# ControllerV1_0_2.net
KiCad netlist of a schematic drawn in Altium Designer
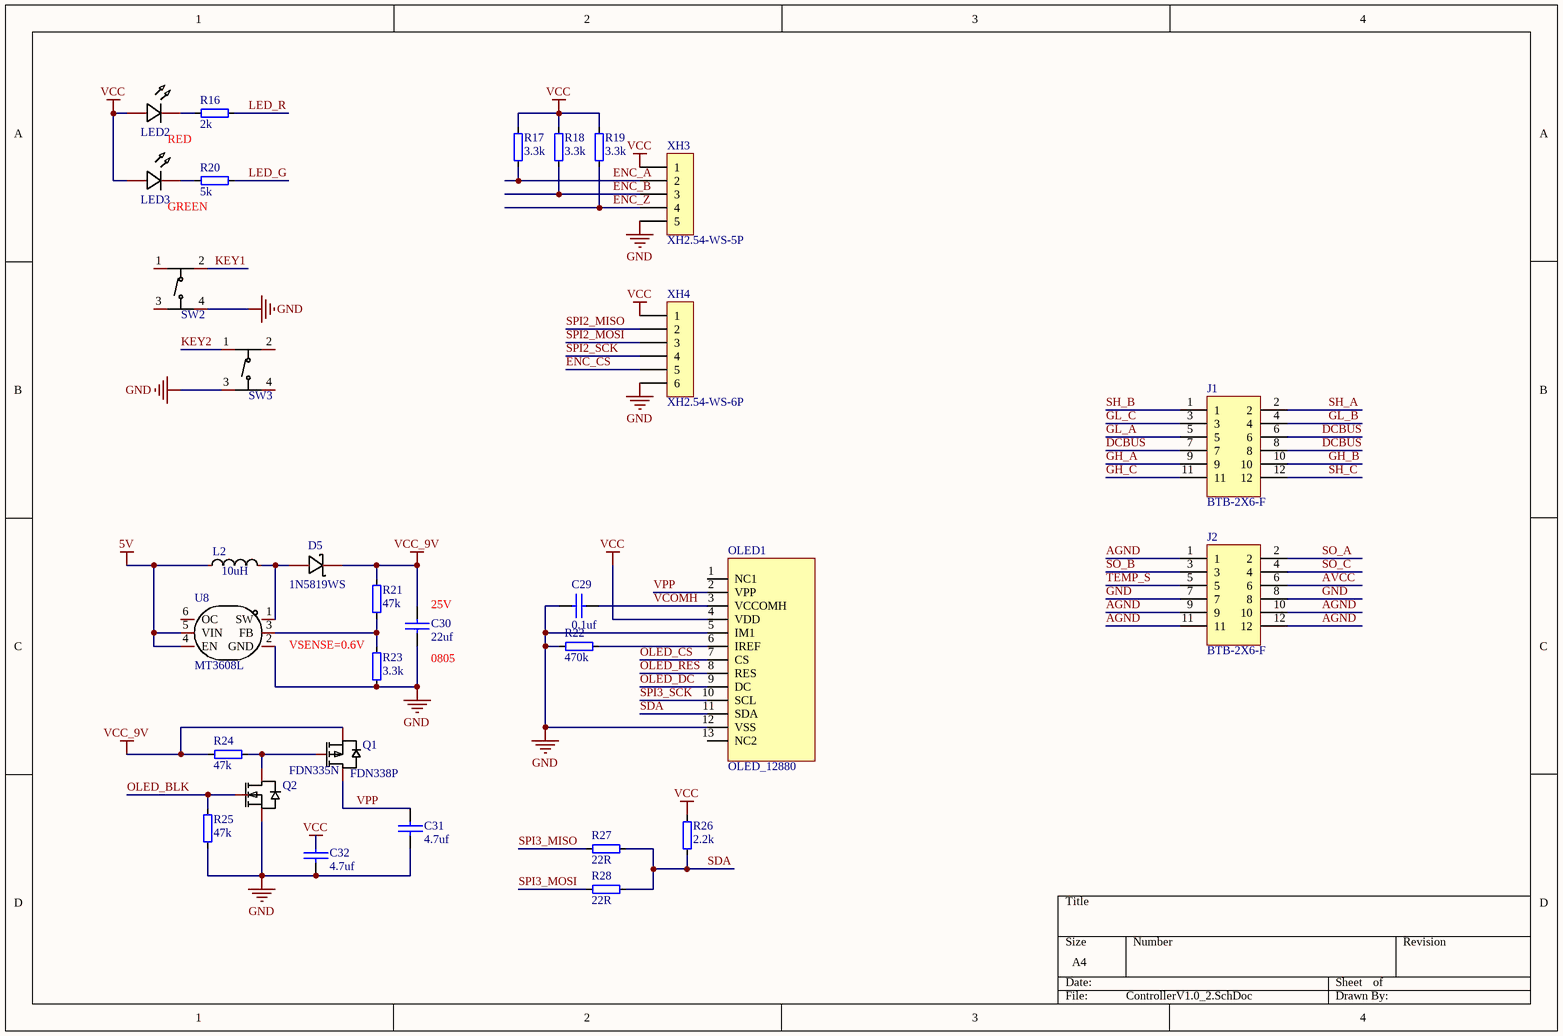
[diagram p0: ControllerV1.0_2.SchDoc]

(export (version "E")
  (design (tool "Eeschema 10.0.6"))
  (components
    (comp (ref "C29")
      (value "0.1uf")
      (footprint "0603C")
      (description "贴片电容")
      (libsource (lib "Controller") (part "CAP"))
    )
    (comp (ref "C30")
      (value "22uf")
      (footprint "0805C")
      (description "贴片电容")
      (libsource (lib "Controller") (part "CAP"))
    )
    (comp (ref "C31")
      (value "4.7uf")
      (footprint "0603C")
      (description "贴片电容")
      (libsource (lib "Controller") (part "CAP"))
    )
    (comp (ref "C32")
      (value "4.7uf")
      (footprint "0603C")
      (description "贴片电容")
      (libsource (lib "Controller") (part "CAP"))
    )
    (comp (ref "D5")
      (value "1N5819WS")
      (footprint "SOD-323")
      (description "肖特基二极管")
      (fields (field (name "MANUFACTURER") "Hottech(合科泰)"))
      (libsource (lib "Controller") (part "1N5819WS"))
    )
    (comp (ref "J1")
      (value "BTB-2X6-F")
      (footprint "BTB-F-0.8mm-2x6P")
      (description "0.8间距2x6P母座")
      (libsource (lib "Controller") (part "BTB-2X6-F"))
    )
    (comp (ref "J2")
      (value "BTB-2X6-F")
      (footprint "BTB-F-0.8mm-2x6P")
      (description "0.8间距2x6P母座")
      (libsource (lib "Controller") (part "BTB-2X6-F"))
    )
    (comp (ref "L2")
      (value "10uH")
      (footprint "IND-SMD_L3.0-W3.0_SWPA3010S")
      (description "电感值:10uH;精度:±20%;额定电流:920mA;")
      (fields (field (name "MANUFACTURER") "SXN(顺翔诺)") (field (name "MANUFACTURER PART") "SMDRI74-220M"))
      (libsource (lib "Controller") (part "SWPA3015S100MT"))
    )
    (comp (ref "LED2")
      (value "LED_0603-B")
      (footprint "LED_0603")
      (libsource (lib "Controller") (part "LED"))
    )
    (comp (ref "LED3")
      (value "LED_0603-B")
      (footprint "LED_0603")
      (libsource (lib "Controller") (part "LED"))
    )
    (comp (ref "OLED1")
      (value "OLED_12880")
      (footprint "OLED_12880")
      (description "OLED_128*80")
      (libsource (lib "Controller") (part "OLED_12880"))
    )
    (comp (ref "Q1")
      (value "FDN338P")
      (footprint "SOT-23-3")
      (description "P沟道 耐压:20V 电流:2A")
      (fields (field (name "MANUFACTURER") "TECH PUBLIC(台舟)"))
      (libsource (lib "Controller") (part "FDN338P"))
    )
    (comp (ref "Q2")
      (value "FDN335N")
      (footprint "SOT-23-3")
      (description "N沟道 耐压:20V 电流:1.7A")
      (fields (field (name "MANUFACTURER") "TECH PUBLIC(台舟)"))
      (libsource (lib "Controller") (part "FDN335N"))
    )
    (comp (ref "R16")
      (value "2k")
      (footprint "0603R")
      (description "贴片电阻")
      (libsource (lib "Controller") (part "RES"))
    )
    (comp (ref "R17")
      (value "3.3k")
      (footprint "0603R")
      (description "贴片电阻")
      (libsource (lib "Controller") (part "RES"))
    )
    (comp (ref "R18")
      (value "3.3k")
      (footprint "0603R")
      (description "贴片电阻")
      (libsource (lib "Controller") (part "RES"))
    )
    (comp (ref "R19")
      (value "3.3k")
      (footprint "0603R")
      (description "贴片电阻")
      (libsource (lib "Controller") (part "RES"))
    )
    (comp (ref "R20")
      (value "5k")
      (footprint "0603R")
      (description "贴片电阻")
      (libsource (lib "Controller") (part "RES"))
    )
    (comp (ref "R21")
      (value "47k")
      (footprint "0603R")
      (description "贴片电阻")
      (libsource (lib "Controller") (part "RES"))
    )
    (comp (ref "R22")
      (value "470k")
      (footprint "0603R")
      (description "贴片电阻")
      (libsource (lib "Controller") (part "RES"))
    )
    (comp (ref "R23")
      (value "3.3k")
      (footprint "0603R")
      (description "贴片电阻")
      (libsource (lib "Controller") (part "RES"))
    )
    (comp (ref "R24")
      (value "47k")
      (footprint "0603R")
      (description "贴片电阻")
      (libsource (lib "Controller") (part "RES"))
    )
    (comp (ref "R25")
      (value "47k")
      (footprint "0603R")
      (description "贴片电阻")
      (libsource (lib "Controller") (part "RES"))
    )
    (comp (ref "R26")
      (value "2.2k")
      (footprint "0603R")
      (description "贴片电阻")
      (libsource (lib "Controller") (part "RES"))
    )
    (comp (ref "R27")
      (value "22R")
      (footprint "0603R")
      (description "贴片电阻")
      (libsource (lib "Controller") (part "RES"))
    )
    (comp (ref "R28")
      (value "22R")
      (footprint "0603R")
      (description "贴片电阻")
      (libsource (lib "Controller") (part "RES"))
    )
    (comp (ref "SW2")
      (value "TS-1187A-B-A-B")
      (footprint "TSW SMD-4*4*1.5")
      (description "轻触开关")
      (fields (field (name "MANUFACTURER") "XKB Connectivity(中国星坤)"))
      (libsource (lib "Controller") (part "TS-1187A-B-A-B"))
    )
    (comp (ref "SW3")
      (value "TS-1187A-B-A-B")
      (footprint "TSW SMD-4*4*1.5")
      (description "轻触开关")
      (fields (field (name "MANUFACTURER") "XKB Connectivity(中国星坤)"))
      (libsource (lib "Controller") (part "TS-1187A-B-A-B"))
    )
    (comp (ref "U8")
      (value "MT3608L")
      (footprint "SOT-23-6")
      (fields (field (name "MANUFACTURER") "西安航天民芯"))
      (libsource (lib "Controller") (part "MT3608L"))
    )
    (comp (ref "XH3")
      (value "XH2.54-WS-5P")
      (footprint "XH2.54-WS-5P")
      (libsource (lib "Controller") (part "XH2.54-WS-5P"))
    )
    (comp (ref "XH4")
      (value "XH2.54-WS-6P")
      (footprint "XH2.54-WS-6P")
      (libsource (lib "Controller") (part "XH2.54-WS-6P"))
    )
  )
  (nets
    (net (code "1") (name "/AGND") (class "Default")
      (node (ref "J2") (pin "1") (pinfunction "1_1") (pintype "passive"))
      (node (ref "J2") (pin "10") (pinfunction "10_10") (pintype "passive"))
      (node (ref "J2") (pin "11") (pinfunction "11_11") (pintype "passive"))
      (node (ref "J2") (pin "12") (pinfunction "12_12") (pintype "passive"))
      (node (ref "J2") (pin "9") (pinfunction "9_9") (pintype "passive"))
    )
    (net (code "2") (name "/AVCC") (class "Default")
      (node (ref "J2") (pin "6") (pinfunction "6_6") (pintype "passive"))
    )
    (net (code "3") (name "/DCBUS") (class "Default")
      (node (ref "J1") (pin "6") (pinfunction "6_6") (pintype "passive"))
      (node (ref "J1") (pin "7") (pinfunction "7_7") (pintype "passive"))
      (node (ref "J1") (pin "8") (pinfunction "8_8") (pintype "passive"))
    )
    (net (code "4") (name "/ENC_A") (class "Default")
      (node (ref "R17") (pin "1") (pinfunction "1_1") (pintype "passive"))
      (node (ref "XH3") (pin "2") (pinfunction "2_2") (pintype "passive"))
    )
    (net (code "5") (name "/ENC_B") (class "Default")
      (node (ref "R18") (pin "1") (pinfunction "1_1") (pintype "passive"))
      (node (ref "XH3") (pin "3") (pinfunction "3_3") (pintype "passive"))
    )
    (net (code "6") (name "/ENC_CS") (class "Default")
      (node (ref "XH4") (pin "5") (pinfunction "5_5") (pintype "passive"))
    )
    (net (code "7") (name "/ENC_Z") (class "Default")
      (node (ref "R19") (pin "1") (pinfunction "1_1") (pintype "passive"))
      (node (ref "XH3") (pin "4") (pinfunction "4_4") (pintype "passive"))
    )
    (net (code "8") (name "/GH_A") (class "Default")
      (node (ref "J1") (pin "9") (pinfunction "9_9") (pintype "passive"))
    )
    (net (code "9") (name "/GH_B") (class "Default")
      (node (ref "J1") (pin "10") (pinfunction "10_10") (pintype "passive"))
    )
    (net (code "10") (name "/GH_C") (class "Default")
      (node (ref "J1") (pin "11") (pinfunction "11_11") (pintype "passive"))
    )
    (net (code "11") (name "/GL_A") (class "Default")
      (node (ref "J1") (pin "5") (pinfunction "5_5") (pintype "passive"))
    )
    (net (code "12") (name "/GL_B") (class "Default")
      (node (ref "J1") (pin "4") (pinfunction "4_4") (pintype "passive"))
    )
    (net (code "13") (name "/GL_C") (class "Default")
      (node (ref "J1") (pin "3") (pinfunction "3_3") (pintype "passive"))
    )
    (net (code "14") (name "/KEY1") (class "Default")
      (node (ref "SW2") (pin "2") (pinfunction "B_2") (pintype "passive"))
    )
    (net (code "15") (name "/KEY2") (class "Default")
      (node (ref "SW3") (pin "1") (pinfunction "A_1") (pintype "passive"))
    )
    (net (code "16") (name "/LED_G") (class "Default")
      (node (ref "R20") (pin "2") (pinfunction "2_2") (pintype "passive"))
    )
    (net (code "17") (name "/LED_R") (class "Default")
      (node (ref "R16") (pin "2") (pinfunction "2_2") (pintype "passive"))
    )
    (net (code "18") (name "/OLED_BLK") (class "Default")
      (node (ref "Q2") (pin "1") (pinfunction "G_1") (pintype "passive"))
      (node (ref "R25") (pin "2") (pinfunction "2_2") (pintype "passive"))
    )
    (net (code "19") (name "/OLED_CS") (class "Default")
      (node (ref "OLED1") (pin "7") (pinfunction "CS_7") (pintype "passive"))
    )
    (net (code "20") (name "/OLED_DC") (class "Default")
      (node (ref "OLED1") (pin "9") (pinfunction "DC_9") (pintype "passive"))
    )
    (net (code "21") (name "/OLED_RES") (class "Default")
      (node (ref "OLED1") (pin "8") (pinfunction "RES_8") (pintype "passive"))
    )
    (net (code "22") (name "/SDA") (class "Default")
      (node (ref "OLED1") (pin "11") (pinfunction "SDA_11") (pintype "passive"))
      (node (ref "R26") (pin "1") (pinfunction "1_1") (pintype "passive"))
      (node (ref "R27") (pin "2") (pinfunction "2_2") (pintype "passive"))
      (node (ref "R28") (pin "2") (pinfunction "2_2") (pintype "passive"))
    )
    (net (code "23") (name "/SH_A") (class "Default")
      (node (ref "J1") (pin "2") (pinfunction "2_2") (pintype "passive"))
    )
    (net (code "24") (name "/SH_B") (class "Default")
      (node (ref "J1") (pin "1") (pinfunction "1_1") (pintype "passive"))
    )
    (net (code "25") (name "/SH_C") (class "Default")
      (node (ref "J1") (pin "12") (pinfunction "12_12") (pintype "passive"))
    )
    (net (code "26") (name "/SO_A") (class "Default")
      (node (ref "J2") (pin "2") (pinfunction "2_2") (pintype "passive"))
    )
    (net (code "27") (name "/SO_B") (class "Default")
      (node (ref "J2") (pin "3") (pinfunction "3_3") (pintype "passive"))
    )
    (net (code "28") (name "/SO_C") (class "Default")
      (node (ref "J2") (pin "4") (pinfunction "4_4") (pintype "passive"))
    )
    (net (code "29") (name "/SPI2_MISO") (class "Default")
      (node (ref "XH4") (pin "2") (pinfunction "2_2") (pintype "passive"))
    )
    (net (code "30") (name "/SPI2_MOSI") (class "Default")
      (node (ref "XH4") (pin "3") (pinfunction "3_3") (pintype "passive"))
    )
    (net (code "31") (name "/SPI2_SCK") (class "Default")
      (node (ref "XH4") (pin "4") (pinfunction "4_4") (pintype "passive"))
    )
    (net (code "32") (name "/SPI3_MISO") (class "Default")
      (node (ref "R27") (pin "1") (pinfunction "1_1") (pintype "passive"))
    )
    (net (code "33") (name "/SPI3_MOSI") (class "Default")
      (node (ref "R28") (pin "1") (pinfunction "1_1") (pintype "passive"))
    )
    (net (code "34") (name "/SPI3_SCK") (class "Default")
      (node (ref "OLED1") (pin "10") (pinfunction "SCL_10") (pintype "passive"))
    )
    (net (code "35") (name "/TEMP_S") (class "Default")
      (node (ref "J2") (pin "5") (pinfunction "5_5") (pintype "passive"))
    )
    (net (code "36") (name "/VCOMH") (class "Default")
      (node (ref "C29") (pin "2") (pinfunction "2_2") (pintype "passive"))
      (node (ref "OLED1") (pin "3") (pinfunction "VCCOMH_3") (pintype "passive"))
    )
    (net (code "37") (name "/VPP") (class "Default")
      (node (ref "C31") (pin "1") (pinfunction "1_1") (pintype "passive"))
      (node (ref "OLED1") (pin "2") (pinfunction "VPP_2") (pintype "passive"))
      (node (ref "Q1") (pin "3") (pinfunction "D_3") (pintype "passive"))
    )
    (net (code "38") (name "5V") (class "Default")
      (node (ref "L2") (pin "1") (pinfunction "1_1") (pintype "passive"))
      (node (ref "U8") (pin "4") (pinfunction "EN_4") (pintype "passive"))
      (node (ref "U8") (pin "5") (pinfunction "VIN_5") (pintype "passive"))
    )
    (net (code "39") (name "GND") (class "Default")
      (node (ref "C29") (pin "1") (pinfunction "1_1") (pintype "passive"))
      (node (ref "C30") (pin "2") (pinfunction "2_2") (pintype "passive"))
      (node (ref "C31") (pin "2") (pinfunction "2_2") (pintype "passive"))
      (node (ref "C32") (pin "2") (pinfunction "2_2") (pintype "passive"))
      (node (ref "J2") (pin "7") (pinfunction "7_7") (pintype "passive"))
      (node (ref "J2") (pin "8") (pinfunction "8_8") (pintype "passive"))
      (node (ref "OLED1") (pin "12") (pinfunction "VSS_12") (pintype "passive"))
      (node (ref "OLED1") (pin "5") (pinfunction "IM1_5") (pintype "passive"))
      (node (ref "Q2") (pin "2") (pinfunction "S_2") (pintype "passive"))
      (node (ref "R22") (pin "1") (pinfunction "1_1") (pintype "passive"))
      (node (ref "R23") (pin "1") (pinfunction "1_1") (pintype "passive"))
      (node (ref "R25") (pin "1") (pinfunction "1_1") (pintype "passive"))
      (node (ref "SW2") (pin "4") (pinfunction "D_4") (pintype "passive"))
      (node (ref "SW3") (pin "3") (pinfunction "C_3") (pintype "passive"))
      (node (ref "U8") (pin "2") (pinfunction "GND_2") (pintype "passive"))
      (node (ref "XH3") (pin "5") (pinfunction "5_5") (pintype "passive"))
      (node (ref "XH4") (pin "6") (pinfunction "6_6") (pintype "passive"))
    )
    (net (code "40") (name "Net-(D5-A)") (class "Default")
      (node (ref "D5") (pin "2") (pinfunction "A_2") (pintype "passive"))
      (node (ref "L2") (pin "2") (pinfunction "2_2") (pintype "passive"))
      (node (ref "U8") (pin "1") (pinfunction "SW_1") (pintype "passive"))
    )
    (net (code "41") (name "Net-(LED2-C)") (class "Default")
      (node (ref "LED2") (pin "1") (pinfunction "C_1") (pintype "passive"))
      (node (ref "R16") (pin "1") (pinfunction "1_1") (pintype "passive"))
    )
    (net (code "42") (name "Net-(LED3-C)") (class "Default")
      (node (ref "LED3") (pin "1") (pinfunction "C_1") (pintype "passive"))
      (node (ref "R20") (pin "1") (pinfunction "1_1") (pintype "passive"))
    )
    (net (code "43") (name "Net-(OLED1-IREF)") (class "Default")
      (node (ref "OLED1") (pin "6") (pinfunction "IREF_6") (pintype "passive"))
      (node (ref "R22") (pin "2") (pinfunction "2_2") (pintype "passive"))
    )
    (net (code "44") (name "Net-(Q1-G)") (class "Default")
      (node (ref "Q1") (pin "1") (pinfunction "G_1") (pintype "passive"))
      (node (ref "Q2") (pin "3") (pinfunction "D_3") (pintype "passive"))
      (node (ref "R24") (pin "2") (pinfunction "2_2") (pintype "passive"))
    )
    (net (code "45") (name "Net-(U8-FB)") (class "Default")
      (node (ref "R21") (pin "1") (pinfunction "1_1") (pintype "passive"))
      (node (ref "R23") (pin "2") (pinfunction "2_2") (pintype "passive"))
      (node (ref "U8") (pin "3") (pinfunction "FB_3") (pintype "passive"))
    )
    (net (code "46") (name "VCC") (class "Default")
      (node (ref "C32") (pin "1") (pinfunction "1_1") (pintype "passive"))
      (node (ref "LED2") (pin "2") (pinfunction "A_2") (pintype "passive"))
      (node (ref "LED3") (pin "2") (pinfunction "A_2") (pintype "passive"))
      (node (ref "OLED1") (pin "4") (pinfunction "VDD_4") (pintype "passive"))
      (node (ref "R17") (pin "2") (pinfunction "2_2") (pintype "passive"))
      (node (ref "R18") (pin "2") (pinfunction "2_2") (pintype "passive"))
      (node (ref "R19") (pin "2") (pinfunction "2_2") (pintype "passive"))
      (node (ref "R26") (pin "2") (pinfunction "2_2") (pintype "passive"))
      (node (ref "XH3") (pin "1") (pinfunction "1_1") (pintype "passive"))
      (node (ref "XH4") (pin "1") (pinfunction "1_1") (pintype "passive"))
    )
    (net (code "47") (name "VCC_9V") (class "Default")
      (node (ref "C30") (pin "1") (pinfunction "1_1") (pintype "passive"))
      (node (ref "D5") (pin "1") (pinfunction "K_1") (pintype "passive"))
      (node (ref "Q1") (pin "2") (pinfunction "S_2") (pintype "passive"))
      (node (ref "R21") (pin "2") (pinfunction "2_2") (pintype "passive"))
      (node (ref "R24") (pin "1") (pinfunction "1_1") (pintype "passive"))
    )
    (net (code "48") (name "unconnected-(OLED1-NC1-Pad1)") (class "Default")
      (node (ref "OLED1") (pin "1") (pinfunction "NC1_1") (pintype "passive"))
    )
    (net (code "49") (name "unconnected-(OLED1-NC2-Pad13)") (class "Default")
      (node (ref "OLED1") (pin "13") (pinfunction "NC2_13") (pintype "passive"))
    )
    (net (code "50") (name "unconnected-(SW2-A-Pad1)") (class "Default")
      (node (ref "SW2") (pin "1") (pinfunction "A_1") (pintype "passive"))
    )
    (net (code "51") (name "unconnected-(SW2-C-Pad3)") (class "Default")
      (node (ref "SW2") (pin "3") (pinfunction "C_3") (pintype "passive"))
    )
    (net (code "52") (name "unconnected-(SW3-B-Pad2)") (class "Default")
      (node (ref "SW3") (pin "2") (pinfunction "B_2") (pintype "passive"))
    )
    (net (code "53") (name "unconnected-(SW3-D-Pad4)") (class "Default")
      (node (ref "SW3") (pin "4") (pinfunction "D_4") (pintype "passive"))
    )
    (net (code "54") (name "unconnected-(U8-OC-Pad6)") (class "Default")
      (node (ref "U8") (pin "6") (pinfunction "OC_6") (pintype "passive"))
    )
  )
)
